# old_control_panel.net
KiCad netlist of a schematic drawn in EAGLE
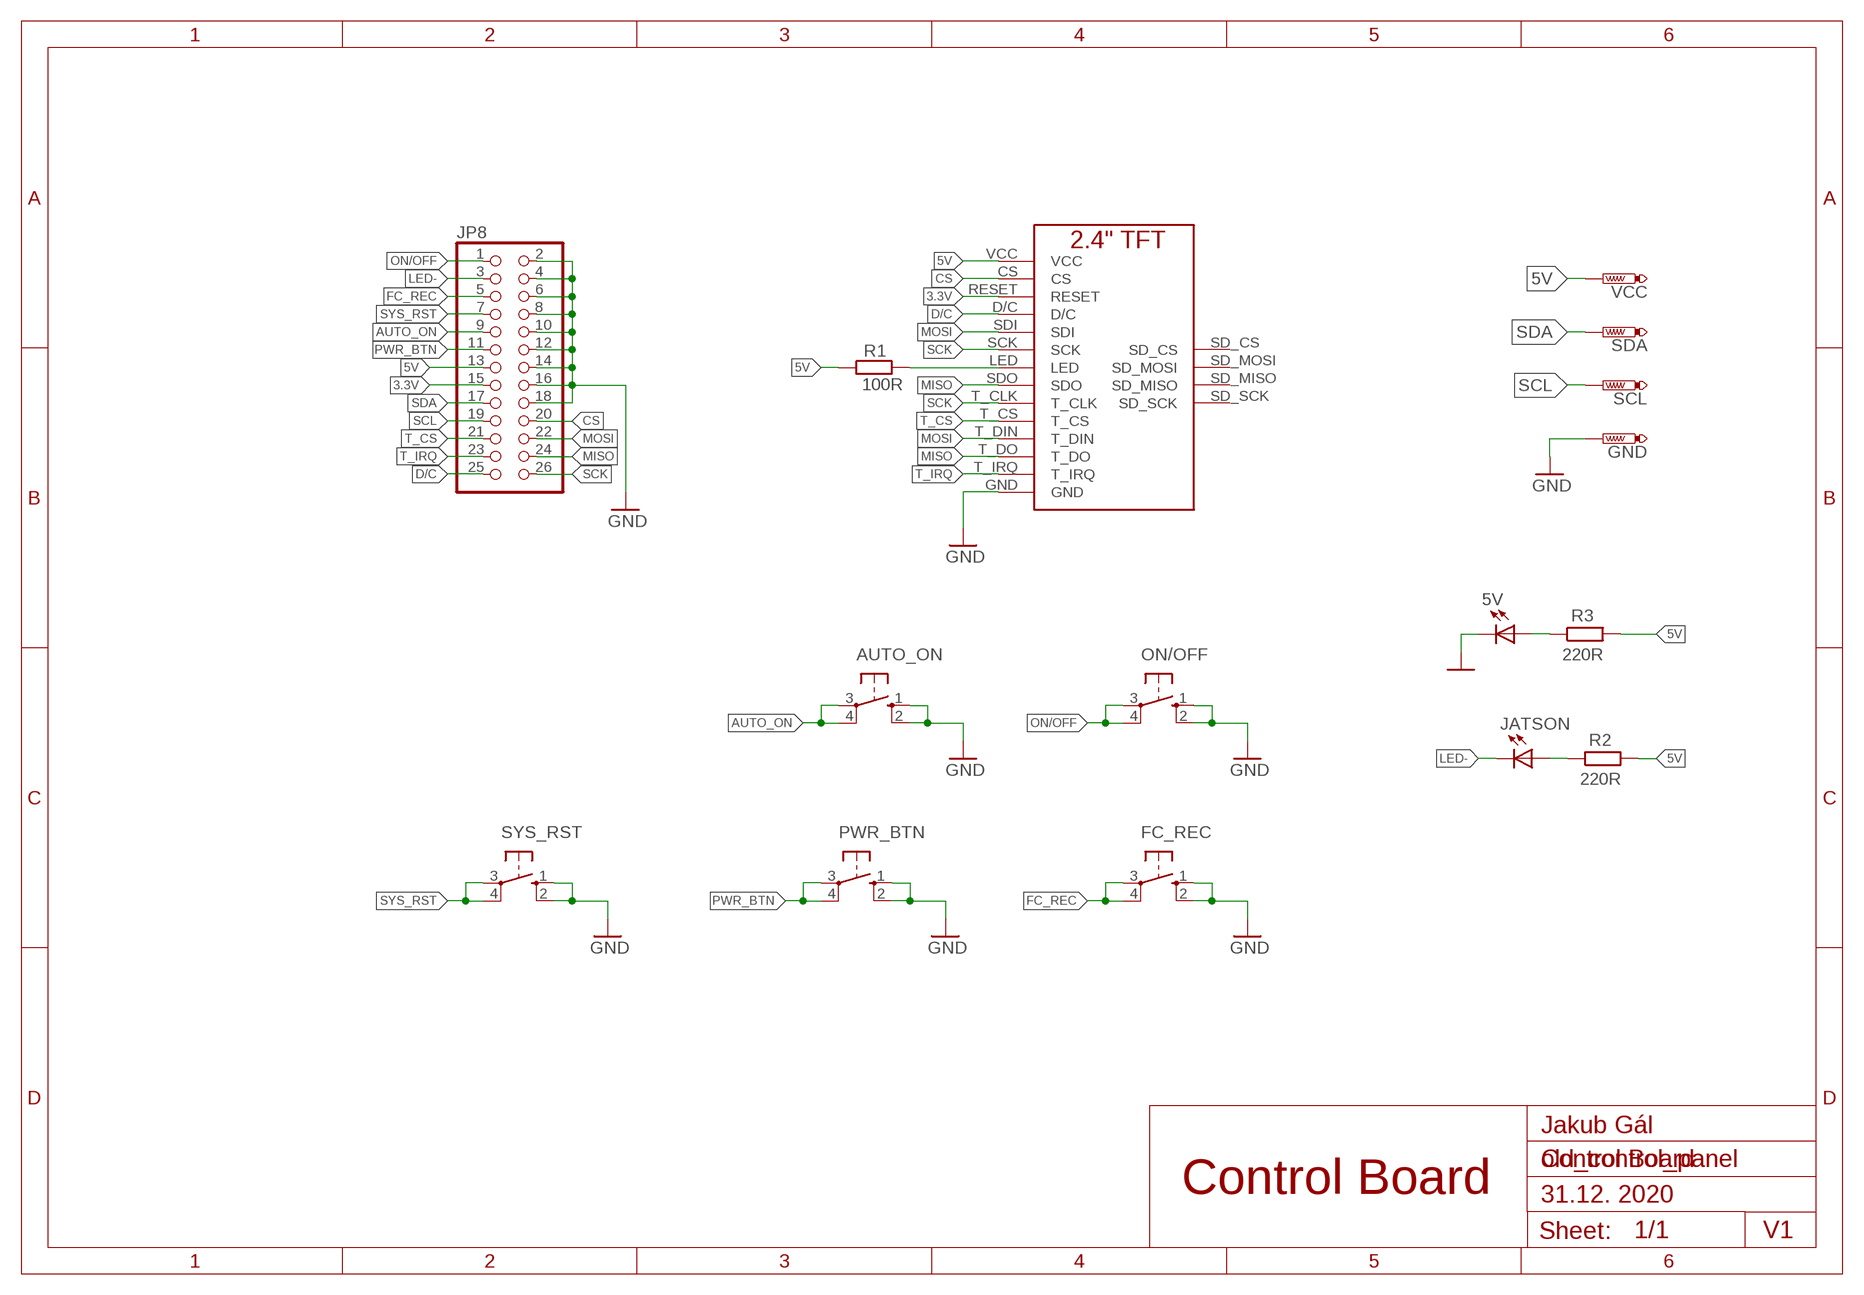
[diagram p0: schematic, sheet 1]

(export (version "E")
  (design (tool "Eeschema 10.0.6"))
  (components
    (comp (ref "5V")
      (value "LEDCHIPLED_0603")
      (footprint "eagle-import:CHIPLED_0603")
      (libsource (lib "eagle-import") (part "LEDCHIPLED_0603"))
    )
    (comp (ref "AUTO_ON")
      (value "10-XX")
      (footprint "eagle-import:B3F-10XX")
      (fields (field (name "MPN") "B3F-1000"))
      (libsource (lib "eagle-import") (part "10-XX"))
    )
    (comp (ref "FC_REC")
      (value "10-XX")
      (footprint "eagle-import:B3F-10XX")
      (fields (field (name "MPN") "B3F-1000"))
      (libsource (lib "eagle-import") (part "10-XX"))
    )
    (comp (ref "GND")
      (value "PTR1TP20R")
      (footprint "eagle-import:TP20R")
      (libsource (lib "eagle-import") (part "PTR1TP20R"))
    )
    (comp (ref "JATSON")
      (value "LEDCHIPLED_0603")
      (footprint "eagle-import:CHIPLED_0603")
      (libsource (lib "eagle-import") (part "LEDCHIPLED_0603"))
    )
    (comp (ref "JP8")
      (value "PINHD-2X13_2.54")
      (footprint "eagle-import:2X13")
      (libsource (lib "eagle-import") (part "PINHD-2X13_2.54"))
    )
    (comp (ref "ON/OFF")
      (value "10-XX")
      (footprint "eagle-import:B3F-10XX")
      (fields (field (name "MPN") "B3F-1000"))
      (libsource (lib "eagle-import") (part "10-XX"))
    )
    (comp (ref "PWR_BTN")
      (value "10-XX")
      (footprint "eagle-import:B3F-10XX")
      (fields (field (name "MPN") "B3F-1000"))
      (libsource (lib "eagle-import") (part "10-XX"))
    )
    (comp (ref "R1")
      (value "100R")
      (footprint "eagle-import:R0603")
      (libsource (lib "eagle-import") (part "R-EU_R0603"))
    )
    (comp (ref "R2")
      (value "220R")
      (footprint "eagle-import:R0603")
      (libsource (lib "eagle-import") (part "R-EU_R0603"))
    )
    (comp (ref "R3")
      (value "220R")
      (footprint "eagle-import:R0603")
      (libsource (lib "eagle-import") (part "R-EU_R0603"))
    )
    (comp (ref "SCL")
      (value "PTR1TP20R")
      (footprint "eagle-import:TP20R")
      (libsource (lib "eagle-import") (part "PTR1TP20R"))
    )
    (comp (ref "SDA")
      (value "PTR1TP20R")
      (footprint "eagle-import:TP20R")
      (libsource (lib "eagle-import") (part "PTR1TP20R"))
    )
    (comp (ref "SYS_RST")
      (value "10-XX")
      (footprint "eagle-import:B3F-10XX")
      (fields (field (name "MPN") "B3F-1000"))
      (libsource (lib "eagle-import") (part "10-XX"))
    )
    (comp (ref "U$1")
      (value "2.4\"TFT")
      (footprint "eagle-import:TFT_2.4_")
      (libsource (lib "eagle-import") (part "2.4{dblquote}TFT"))
    )
    (comp (ref "VCC")
      (value "PTR1TP20R")
      (footprint "eagle-import:TP20R")
      (libsource (lib "eagle-import") (part "PTR1TP20R"))
    )
  )
  (nets
    (net (code "1") (name "3.3V") (class "Default")
      (node (ref "JP8") (pin "15") (pinfunction "15_15") (pintype "passive"))
      (node (ref "U$1") (pin "RESET") (pinfunction "RESET_RESET") (pintype "bidirectional"))
    )
    (net (code "2") (name "5V") (class "Default")
      (node (ref "JP8") (pin "13") (pinfunction "13_13") (pintype "passive"))
      (node (ref "R1") (pin "1") (pinfunction "1_1") (pintype "passive"))
      (node (ref "R2") (pin "2") (pinfunction "2_2") (pintype "passive"))
      (node (ref "R3") (pin "2") (pinfunction "2_2") (pintype "passive"))
      (node (ref "U$1") (pin "VCC") (pinfunction "VCC_VCC") (pintype "bidirectional"))
      (node (ref "VCC") (pin "TP") (pinfunction "TP_TP") (pintype "input"))
    )
    (net (code "3") (name "AUTO_ON") (class "Default")
      (node (ref "AUTO_ON") (pin "3") (pinfunction "P_3") (pintype "passive"))
      (node (ref "AUTO_ON") (pin "4") (pinfunction "P1_4") (pintype "passive"))
      (node (ref "JP8") (pin "9") (pinfunction "9_9") (pintype "passive"))
    )
    (net (code "4") (name "CS") (class "Default")
      (node (ref "JP8") (pin "20") (pinfunction "20_20") (pintype "passive"))
      (node (ref "U$1") (pin "CS") (pinfunction "CS_CS") (pintype "bidirectional"))
    )
    (net (code "5") (name "D{slash}C") (class "Default")
      (node (ref "JP8") (pin "25") (pinfunction "25_25") (pintype "passive"))
      (node (ref "U$1") (pin "D/C") (pinfunction "D/C_D/C") (pintype "bidirectional"))
    )
    (net (code "6") (name "FC_REC") (class "Default")
      (node (ref "FC_REC") (pin "3") (pinfunction "P_3") (pintype "passive"))
      (node (ref "FC_REC") (pin "4") (pinfunction "P1_4") (pintype "passive"))
      (node (ref "JP8") (pin "5") (pinfunction "5_5") (pintype "passive"))
    )
    (net (code "7") (name "GND") (class "Default")
      (node (ref "5V") (pin "C") (pinfunction "C_C") (pintype "passive"))
      (node (ref "AUTO_ON") (pin "1") (pinfunction "S_1") (pintype "passive"))
      (node (ref "AUTO_ON") (pin "2") (pinfunction "S1_2") (pintype "passive"))
      (node (ref "FC_REC") (pin "1") (pinfunction "S_1") (pintype "passive"))
      (node (ref "FC_REC") (pin "2") (pinfunction "S1_2") (pintype "passive"))
      (node (ref "GND") (pin "TP") (pinfunction "TP_TP") (pintype "input"))
      (node (ref "JP8") (pin "10") (pinfunction "10_10") (pintype "passive"))
      (node (ref "JP8") (pin "12") (pinfunction "12_12") (pintype "passive"))
      (node (ref "JP8") (pin "14") (pinfunction "14_14") (pintype "passive"))
      (node (ref "JP8") (pin "16") (pinfunction "16_16") (pintype "passive"))
      (node (ref "JP8") (pin "18") (pinfunction "18_18") (pintype "passive"))
      (node (ref "JP8") (pin "2") (pinfunction "2_2") (pintype "passive"))
      (node (ref "JP8") (pin "4") (pinfunction "4_4") (pintype "passive"))
      (node (ref "JP8") (pin "6") (pinfunction "6_6") (pintype "passive"))
      (node (ref "JP8") (pin "8") (pinfunction "8_8") (pintype "passive"))
      (node (ref "ON/OFF") (pin "1") (pinfunction "S_1") (pintype "passive"))
      (node (ref "ON/OFF") (pin "2") (pinfunction "S1_2") (pintype "passive"))
      (node (ref "PWR_BTN") (pin "1") (pinfunction "S_1") (pintype "passive"))
      (node (ref "PWR_BTN") (pin "2") (pinfunction "S1_2") (pintype "passive"))
      (node (ref "SYS_RST") (pin "1") (pinfunction "S_1") (pintype "passive"))
      (node (ref "SYS_RST") (pin "2") (pinfunction "S1_2") (pintype "passive"))
      (node (ref "U$1") (pin "GND") (pinfunction "GND_GND") (pintype "bidirectional"))
    )
    (net (code "8") (name "LED-") (class "Default")
      (node (ref "JATSON") (pin "C") (pinfunction "C_C") (pintype "passive"))
      (node (ref "JP8") (pin "3") (pinfunction "3_3") (pintype "passive"))
    )
    (net (code "9") (name "MISO") (class "Default")
      (node (ref "JP8") (pin "24") (pinfunction "24_24") (pintype "passive"))
      (node (ref "U$1") (pin "SDO") (pinfunction "SDO_SDO") (pintype "bidirectional"))
      (node (ref "U$1") (pin "T_DO") (pinfunction "T_DO_T_DO") (pintype "bidirectional"))
    )
    (net (code "10") (name "MOSI") (class "Default")
      (node (ref "JP8") (pin "22") (pinfunction "22_22") (pintype "passive"))
      (node (ref "U$1") (pin "SDI") (pinfunction "SDI_SDI") (pintype "bidirectional"))
      (node (ref "U$1") (pin "T_DIN") (pinfunction "T_DIN_T_DIN") (pintype "bidirectional"))
    )
    (net (code "11") (name "Net-(5V-PadA)") (class "Default")
      (node (ref "5V") (pin "A") (pinfunction "A_A") (pintype "passive"))
      (node (ref "R3") (pin "1") (pinfunction "1_1") (pintype "passive"))
    )
    (net (code "12") (name "Net-(JATSON-PadA)") (class "Default")
      (node (ref "JATSON") (pin "A") (pinfunction "A_A") (pintype "passive"))
      (node (ref "R2") (pin "1") (pinfunction "1_1") (pintype "passive"))
    )
    (net (code "13") (name "Net-(R1-Pad2)") (class "Default")
      (node (ref "R1") (pin "2") (pinfunction "2_2") (pintype "passive"))
      (node (ref "U$1") (pin "LED") (pinfunction "LED_LED") (pintype "bidirectional"))
    )
    (net (code "14") (name "ON{slash}OFF") (class "Default")
      (node (ref "JP8") (pin "1") (pinfunction "1_1") (pintype "passive"))
      (node (ref "ON/OFF") (pin "3") (pinfunction "P_3") (pintype "passive"))
      (node (ref "ON/OFF") (pin "4") (pinfunction "P1_4") (pintype "passive"))
    )
    (net (code "15") (name "PWR_BTN") (class "Default")
      (node (ref "JP8") (pin "11") (pinfunction "11_11") (pintype "passive"))
      (node (ref "PWR_BTN") (pin "3") (pinfunction "P_3") (pintype "passive"))
      (node (ref "PWR_BTN") (pin "4") (pinfunction "P1_4") (pintype "passive"))
    )
    (net (code "16") (name "SCK") (class "Default")
      (node (ref "JP8") (pin "26") (pinfunction "26_26") (pintype "passive"))
      (node (ref "U$1") (pin "SCK") (pinfunction "SCK_SCK") (pintype "bidirectional"))
      (node (ref "U$1") (pin "T_CLK") (pinfunction "T_CLK_T_CLK") (pintype "bidirectional"))
    )
    (net (code "17") (name "SCL") (class "Default")
      (node (ref "JP8") (pin "19") (pinfunction "19_19") (pintype "passive"))
      (node (ref "SCL") (pin "TP") (pinfunction "TP_TP") (pintype "input"))
    )
    (net (code "18") (name "SDA") (class "Default")
      (node (ref "JP8") (pin "17") (pinfunction "17_17") (pintype "passive"))
      (node (ref "SDA") (pin "TP") (pinfunction "TP_TP") (pintype "input"))
    )
    (net (code "19") (name "SYS_RST") (class "Default")
      (node (ref "JP8") (pin "7") (pinfunction "7_7") (pintype "passive"))
      (node (ref "SYS_RST") (pin "3") (pinfunction "P_3") (pintype "passive"))
      (node (ref "SYS_RST") (pin "4") (pinfunction "P1_4") (pintype "passive"))
    )
    (net (code "20") (name "T_CS") (class "Default")
      (node (ref "JP8") (pin "21") (pinfunction "21_21") (pintype "passive"))
      (node (ref "U$1") (pin "T_CS") (pinfunction "T_CS_T_CS") (pintype "bidirectional"))
    )
    (net (code "21") (name "T_IRQ") (class "Default")
      (node (ref "JP8") (pin "23") (pinfunction "23_23") (pintype "passive"))
      (node (ref "U$1") (pin "T_IRQ") (pinfunction "T_IRQ_T_IRQ") (pintype "bidirectional"))
    )
    (net (code "22") (name "unconnected-(U$1-PadSD_CS)") (class "Default")
      (node (ref "U$1") (pin "SD_CS") (pinfunction "SD_CS_SD_CS") (pintype "bidirectional"))
    )
    (net (code "23") (name "unconnected-(U$1-PadSD_MISO)") (class "Default")
      (node (ref "U$1") (pin "SD_MISO") (pinfunction "SD_MISO_SD_MISO") (pintype "bidirectional"))
    )
    (net (code "24") (name "unconnected-(U$1-PadSD_MOSI)") (class "Default")
      (node (ref "U$1") (pin "SD_MOSI") (pinfunction "SD_MOSI_SD_MOSI") (pintype "bidirectional"))
    )
    (net (code "25") (name "unconnected-(U$1-PadSD_SCK)") (class "Default")
      (node (ref "U$1") (pin "SD_SCK") (pinfunction "SD_SCK_SD_SCK") (pintype "bidirectional"))
    )
  )
)
